# edge.net
KiCad netlist of a schematic drawn in Altium Designer
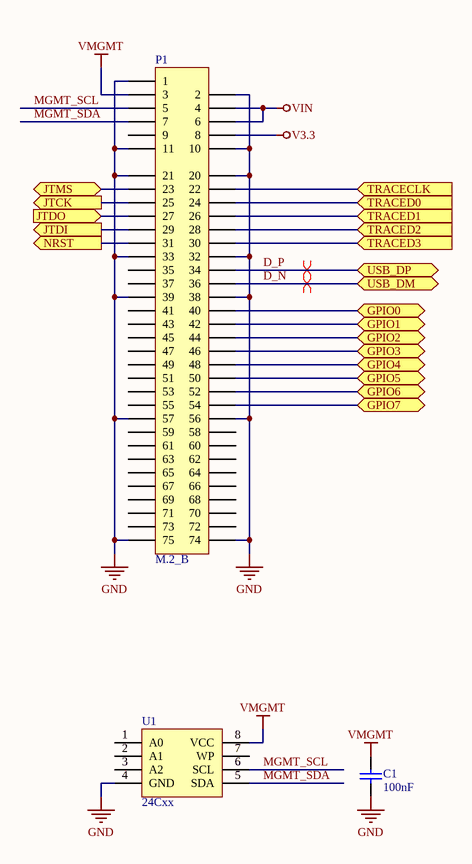
[diagram p0: edge.SchDoc]

(export (version "E")
  (design (tool "Eeschema 10.0.6"))
  (components
    (comp (ref "C1") (value "100nF") (footprint "0402") (libsource (lib "misc") (part "Capacitor")))
    (comp (ref "P1") (value "M.2_B") (footprint "M.2_B_EDGE") (libsource (lib "misc") (part "M.2_B")))
    (comp (ref "U1") (value "24Cxx") (footprint "SO8") (libsource (lib "misc") (part "24Cxx")))
  )
  (nets
    (net (code "1") (name "/D_N") (class "Default")
      (node (ref "P1") (pin "36") (pinfunction "36_36") (pintype "passive"))
    )
    (net (code "2") (name "/D_P") (class "Default")
      (node (ref "P1") (pin "34") (pinfunction "34_34") (pintype "passive"))
    )
    (net (code "3") (name "/GPIO0") (class "Default")
      (node (ref "P1") (pin "40") (pinfunction "40_40") (pintype "passive"))
    )
    (net (code "4") (name "/GPIO1") (class "Default")
      (node (ref "P1") (pin "42") (pinfunction "42_42") (pintype "passive"))
    )
    (net (code "5") (name "/GPIO2") (class "Default")
      (node (ref "P1") (pin "44") (pinfunction "44_44") (pintype "passive"))
    )
    (net (code "6") (name "/GPIO3") (class "Default")
      (node (ref "P1") (pin "46") (pinfunction "46_46") (pintype "passive"))
    )
    (net (code "7") (name "/GPIO4") (class "Default")
      (node (ref "P1") (pin "48") (pinfunction "48_48") (pintype "passive"))
    )
    (net (code "8") (name "/GPIO5") (class "Default")
      (node (ref "P1") (pin "50") (pinfunction "50_50") (pintype "passive"))
    )
    (net (code "9") (name "/GPIO6") (class "Default")
      (node (ref "P1") (pin "52") (pinfunction "52_52") (pintype "passive"))
    )
    (net (code "10") (name "/GPIO7") (class "Default")
      (node (ref "P1") (pin "54") (pinfunction "54_54") (pintype "passive"))
    )
    (net (code "11") (name "/JTCK") (class "Default")
      (node (ref "P1") (pin "25") (pinfunction "25_25") (pintype "passive"))
    )
    (net (code "12") (name "/JTDI") (class "Default")
      (node (ref "P1") (pin "29") (pinfunction "29_29") (pintype "passive"))
    )
    (net (code "13") (name "/JTDO") (class "Default")
      (node (ref "P1") (pin "27") (pinfunction "27_27") (pintype "passive"))
    )
    (net (code "14") (name "/JTMS") (class "Default")
      (node (ref "P1") (pin "23") (pinfunction "23_23") (pintype "passive"))
    )
    (net (code "15") (name "/MGMT_SCL") (class "Default")
      (node (ref "P1") (pin "5") (pinfunction "5_5") (pintype "passive"))
      (node (ref "U1") (pin "6") (pinfunction "SCL_6") (pintype "passive"))
    )
    (net (code "16") (name "/MGMT_SDA") (class "Default")
      (node (ref "P1") (pin "7") (pinfunction "7_7") (pintype "passive"))
      (node (ref "U1") (pin "5") (pinfunction "SDA_5") (pintype "passive"))
    )
    (net (code "17") (name "/NRST") (class "Default")
      (node (ref "P1") (pin "31") (pinfunction "31_31") (pintype "passive"))
    )
    (net (code "18") (name "/TRACECLK") (class "Default")
      (node (ref "P1") (pin "22") (pinfunction "22_22") (pintype "passive"))
    )
    (net (code "19") (name "/TRACED0") (class "Default")
      (node (ref "P1") (pin "24") (pinfunction "24_24") (pintype "passive"))
    )
    (net (code "20") (name "/TRACED1") (class "Default")
      (node (ref "P1") (pin "26") (pinfunction "26_26") (pintype "passive"))
    )
    (net (code "21") (name "/TRACED2") (class "Default")
      (node (ref "P1") (pin "28") (pinfunction "28_28") (pintype "passive"))
    )
    (net (code "22") (name "/TRACED3") (class "Default")
      (node (ref "P1") (pin "30") (pinfunction "30_30") (pintype "passive"))
    )
    (net (code "23") (name "GND") (class "Default")
      (node (ref "C1") (pin "1") (pinfunction "1_1") (pintype "passive"))
      (node (ref "P1") (pin "1") (pinfunction "1_1") (pintype "passive"))
      (node (ref "P1") (pin "10") (pinfunction "10_10") (pintype "passive"))
      (node (ref "P1") (pin "11") (pinfunction "11_11") (pintype "passive"))
      (node (ref "P1") (pin "2") (pinfunction "2_2") (pintype "passive"))
      (node (ref "P1") (pin "20") (pinfunction "20_20") (pintype "passive"))
      (node (ref "P1") (pin "21") (pinfunction "21_21") (pintype "passive"))
      (node (ref "P1") (pin "32") (pinfunction "32_32") (pintype "passive"))
      (node (ref "P1") (pin "33") (pinfunction "33_33") (pintype "passive"))
      (node (ref "P1") (pin "38") (pinfunction "38_38") (pintype "passive"))
      (node (ref "P1") (pin "39") (pinfunction "39_39") (pintype "passive"))
      (node (ref "P1") (pin "56") (pinfunction "56_56") (pintype "passive"))
      (node (ref "P1") (pin "57") (pinfunction "57_57") (pintype "passive"))
      (node (ref "P1") (pin "74") (pinfunction "74_74") (pintype "passive"))
      (node (ref "P1") (pin "75") (pinfunction "75_75") (pintype "passive"))
      (node (ref "U1") (pin "4") (pinfunction "GND_4") (pintype "passive"))
    )
    (net (code "24") (name "V3.3") (class "Default")
      (node (ref "P1") (pin "8") (pinfunction "8_8") (pintype "passive"))
    )
    (net (code "25") (name "VIN") (class "Default")
      (node (ref "P1") (pin "4") (pinfunction "4_4") (pintype "passive"))
      (node (ref "P1") (pin "6") (pinfunction "6_6") (pintype "passive"))
    )
    (net (code "26") (name "VMGMT") (class "Default")
      (node (ref "C1") (pin "2") (pinfunction "2_2") (pintype "passive"))
      (node (ref "P1") (pin "3") (pinfunction "3_3") (pintype "passive"))
      (node (ref "U1") (pin "8") (pinfunction "VCC_8") (pintype "passive"))
    )
    (net (code "27") (name "unconnected-(P1-Pad9)") (class "Default")
      (node (ref "P1") (pin "9") (pinfunction "9_9") (pintype "passive"))
    )
    (net (code "28") (name "unconnected-(P1-Pad35)") (class "Default")
      (node (ref "P1") (pin "35") (pinfunction "35_35") (pintype "passive"))
    )
    (net (code "29") (name "unconnected-(P1-Pad37)") (class "Default")
      (node (ref "P1") (pin "37") (pinfunction "37_37") (pintype "passive"))
    )
    (net (code "30") (name "unconnected-(P1-Pad41)") (class "Default")
      (node (ref "P1") (pin "41") (pinfunction "41_41") (pintype "passive"))
    )
    (net (code "31") (name "unconnected-(P1-Pad43)") (class "Default")
      (node (ref "P1") (pin "43") (pinfunction "43_43") (pintype "passive"))
    )
    (net (code "32") (name "unconnected-(P1-Pad45)") (class "Default")
      (node (ref "P1") (pin "45") (pinfunction "45_45") (pintype "passive"))
    )
    (net (code "33") (name "unconnected-(P1-Pad47)") (class "Default")
      (node (ref "P1") (pin "47") (pinfunction "47_47") (pintype "passive"))
    )
    (net (code "34") (name "unconnected-(P1-Pad49)") (class "Default")
      (node (ref "P1") (pin "49") (pinfunction "49_49") (pintype "passive"))
    )
    (net (code "35") (name "unconnected-(P1-Pad51)") (class "Default")
      (node (ref "P1") (pin "51") (pinfunction "51_51") (pintype "passive"))
    )
    (net (code "36") (name "unconnected-(P1-Pad53)") (class "Default")
      (node (ref "P1") (pin "53") (pinfunction "53_53") (pintype "passive"))
    )
    (net (code "37") (name "unconnected-(P1-Pad55)") (class "Default")
      (node (ref "P1") (pin "55") (pinfunction "55_55") (pintype "passive"))
    )
    (net (code "38") (name "unconnected-(P1-Pad58)") (class "Default")
      (node (ref "P1") (pin "58") (pinfunction "58_58") (pintype "passive"))
    )
    (net (code "39") (name "unconnected-(P1-Pad59)") (class "Default")
      (node (ref "P1") (pin "59") (pinfunction "59_59") (pintype "passive"))
    )
    (net (code "40") (name "unconnected-(P1-Pad60)") (class "Default")
      (node (ref "P1") (pin "60") (pinfunction "60_60") (pintype "passive"))
    )
    (net (code "41") (name "unconnected-(P1-Pad61)") (class "Default")
      (node (ref "P1") (pin "61") (pinfunction "61_61") (pintype "passive"))
    )
    (net (code "42") (name "unconnected-(P1-Pad62)") (class "Default")
      (node (ref "P1") (pin "62") (pinfunction "62_62") (pintype "passive"))
    )
    (net (code "43") (name "unconnected-(P1-Pad63)") (class "Default")
      (node (ref "P1") (pin "63") (pinfunction "63_63") (pintype "passive"))
    )
    (net (code "44") (name "unconnected-(P1-Pad64)") (class "Default")
      (node (ref "P1") (pin "64") (pinfunction "64_64") (pintype "passive"))
    )
    (net (code "45") (name "unconnected-(P1-Pad65)") (class "Default")
      (node (ref "P1") (pin "65") (pinfunction "65_65") (pintype "passive"))
    )
    (net (code "46") (name "unconnected-(P1-Pad66)") (class "Default")
      (node (ref "P1") (pin "66") (pinfunction "66_66") (pintype "passive"))
    )
    (net (code "47") (name "unconnected-(P1-Pad67)") (class "Default")
      (node (ref "P1") (pin "67") (pinfunction "67_67") (pintype "passive"))
    )
    (net (code "48") (name "unconnected-(P1-Pad68)") (class "Default")
      (node (ref "P1") (pin "68") (pinfunction "68_68") (pintype "passive"))
    )
    (net (code "49") (name "unconnected-(P1-Pad69)") (class "Default")
      (node (ref "P1") (pin "69") (pinfunction "69_69") (pintype "passive"))
    )
    (net (code "50") (name "unconnected-(P1-Pad70)") (class "Default")
      (node (ref "P1") (pin "70") (pinfunction "70_70") (pintype "passive"))
    )
    (net (code "51") (name "unconnected-(P1-Pad71)") (class "Default")
      (node (ref "P1") (pin "71") (pinfunction "71_71") (pintype "passive"))
    )
    (net (code "52") (name "unconnected-(P1-Pad72)") (class "Default")
      (node (ref "P1") (pin "72") (pinfunction "72_72") (pintype "passive"))
    )
    (net (code "53") (name "unconnected-(P1-Pad73)") (class "Default")
      (node (ref "P1") (pin "73") (pinfunction "73_73") (pintype "passive"))
    )
    (net (code "54") (name "unconnected-(U1-A0-Pad1)") (class "Default")
      (node (ref "U1") (pin "1") (pinfunction "A0_1") (pintype "passive"))
    )
    (net (code "55") (name "unconnected-(U1-A1-Pad2)") (class "Default")
      (node (ref "U1") (pin "2") (pinfunction "A1_2") (pintype "passive"))
    )
    (net (code "56") (name "unconnected-(U1-A2-Pad3)") (class "Default")
      (node (ref "U1") (pin "3") (pinfunction "A2_3") (pintype "passive"))
    )
    (net (code "57") (name "unconnected-(U1-WP-Pad7)") (class "Default")
      (node (ref "U1") (pin "7") (pinfunction "WP_7") (pintype "passive"))
    )
  )
)
